# MSXII_SteeringWheelSchematic.net
KiCad netlist of a schematic drawn in Altium Designer
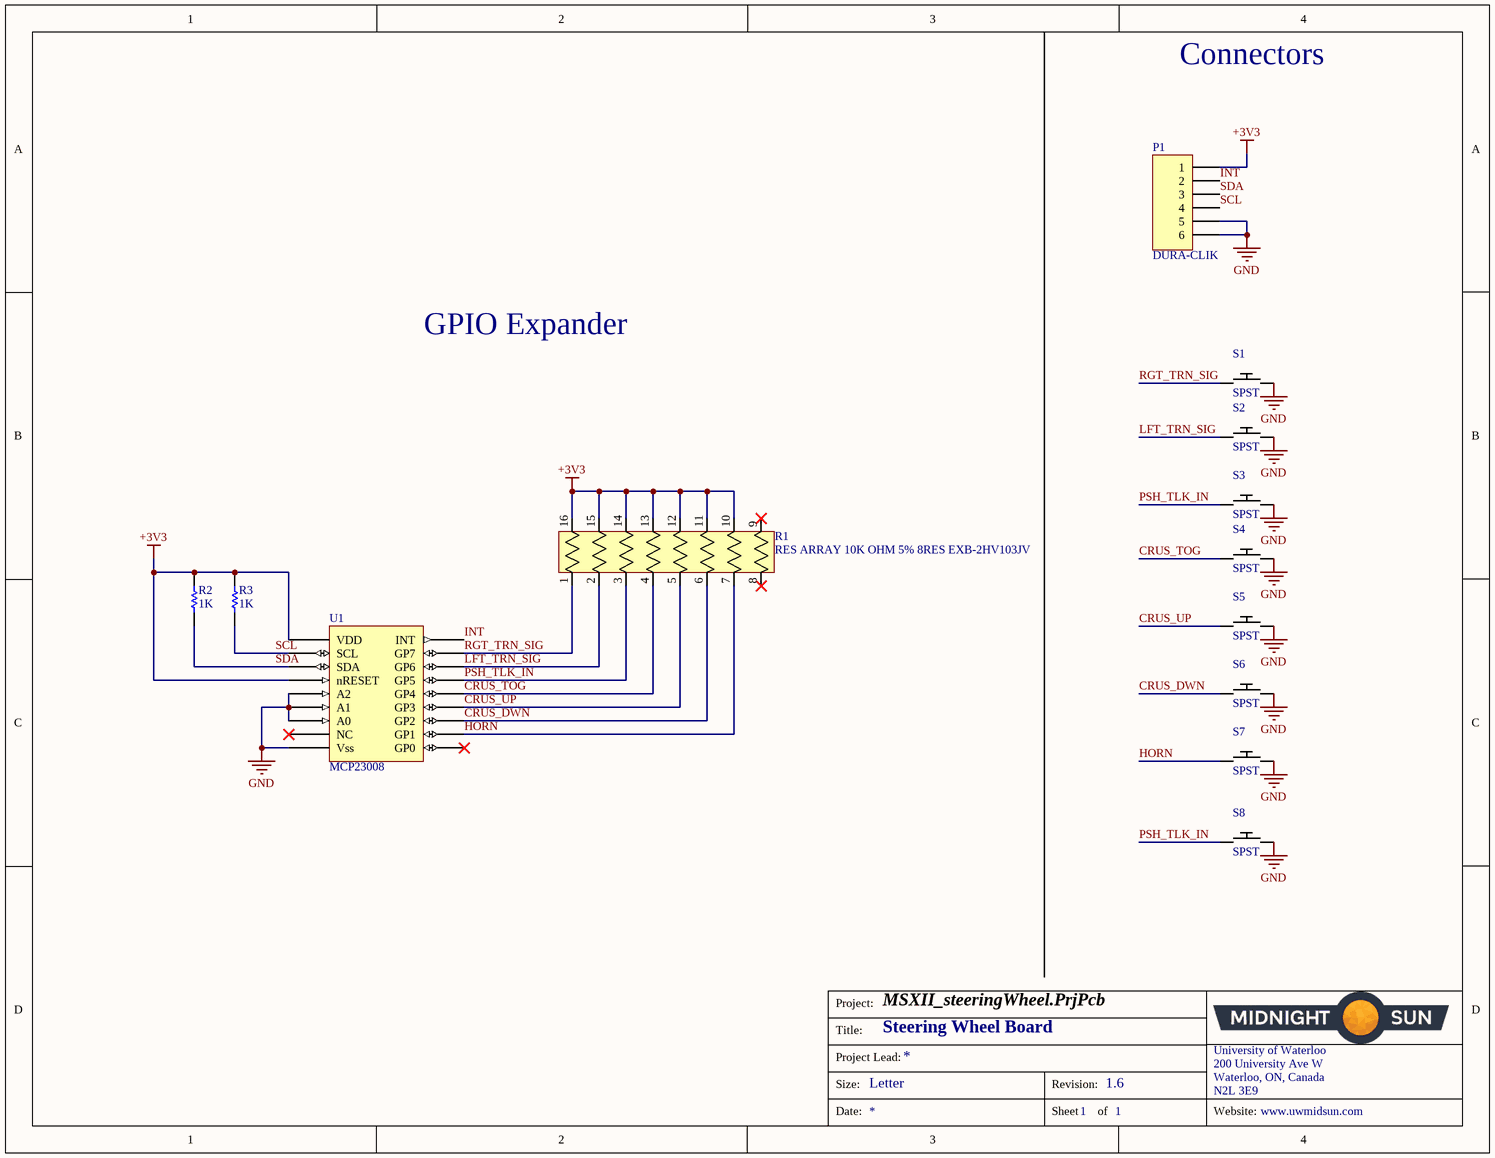
[diagram p0: MSXII_SteeringWheelSchematic.SchDoc]

(export (version "E")
  (design (tool "Eeschema 10.0.6"))
  (components
    (comp (ref "P1")
      (value "DURA-CLIK")
      (footprint "CONN, 6POS DURA-CLIK VERT")
      (description "6 Positions Header, Shrouded Connector 0.079\" (2.00mm) Surface Mount, Vertical Tin")
      (fields (field (name "MANUFACTURER") "Molex") (field (name "MANUFACTURER PART NUMBER") "5600200820"))
      (libsource (lib "Schematic Diagrams") (part "CONN 6POS DURA-CLIK 0.079{dblquote}"))
    )
    (comp (ref "R1")
      (value "RES ARRAY 10K OHM 5% 8RES EXB-2HV103JV")
      (footprint "RES ARRAY, 8 POS 1506")
      (description "RES ARRAY SMD 10K 5% 62.5mW 1506")
      (fields
        (field (name "MANUFACTURER_PART_NUMBER") "EXB-2HV103JV")
        (field (name "COPYRIGHT") "Copyright (C) 2015 Accelerated Designs. All rights reserved")
      )
      (libsource (lib "Schematic Diagrams") (part "RES ARRAY 10K OHM 5% 8RES EXB-2HV103JV"))
    )
    (comp (ref "R2")
      (value "1K")
      (footprint "RES, 0603")
      (description "1k Ohm ±5% 0.1W, 1/10W Chip Resistor 0603 (1608 Metric)")
      (libsource (lib "Schematic Diagrams") (part "RES 1K OHM 5% 1/10W 0603"))
    )
    (comp (ref "R3")
      (value "1K")
      (footprint "RES, 0603")
      (description "1k Ohm ±5% 0.1W, 1/10W Chip Resistor 0603 (1608 Metric)")
      (libsource (lib "Schematic Diagrams") (part "RES 1K OHM 5% 1/10W 0603"))
    )
    (comp (ref "S1")
      (value "SPST")
      (footprint "SW SPST-NO 6x6mm Via Hole")
      (description "Switch Tactile SPST 6x6x9.5mm 15VDC@0.02A Through Hole")
      (libsource (lib "Schematic Diagrams") (part "SW SPST-NO 15VDC@0.02A via hole"))
    )
    (comp (ref "S2")
      (value "SPST")
      (footprint "SW SPST-NO 6x6mm Via Hole")
      (description "Switch Tactile SPST 6x6x9.5mm 15VDC@0.02A Through Hole")
      (libsource (lib "Schematic Diagrams") (part "SW SPST-NO 15VDC@0.02A via hole"))
    )
    (comp (ref "S3")
      (value "SPST")
      (footprint "SW SPST-NO 6x6mm Via Hole")
      (description "Switch Tactile SPST 6x6x9.5mm 15VDC@0.02A Through Hole")
      (libsource (lib "Schematic Diagrams") (part "SW SPST-NO 15VDC@0.02A via hole"))
    )
    (comp (ref "S4")
      (value "SPST")
      (footprint "SW SPST-NO 6x6mm Via Hole")
      (description "Switch Tactile SPST 6x6x9.5mm 15VDC@0.02A Through Hole")
      (libsource (lib "Schematic Diagrams") (part "SW SPST-NO 15VDC@0.02A via hole"))
    )
    (comp (ref "S5")
      (value "SPST")
      (footprint "SW SPST-NO 6x6mm Via Hole")
      (description "Switch Tactile SPST 6x6x9.5mm 15VDC@0.02A Through Hole")
      (libsource (lib "Schematic Diagrams") (part "SW SPST-NO 15VDC@0.02A via hole"))
    )
    (comp (ref "S6")
      (value "SPST")
      (footprint "SW SPST-NO 6x6mm Via Hole")
      (description "Switch Tactile SPST 6x6x9.5mm 15VDC@0.02A Through Hole")
      (libsource (lib "Schematic Diagrams") (part "SW SPST-NO 15VDC@0.02A via hole"))
    )
    (comp (ref "S7")
      (value "SPST")
      (footprint "SW SPST-NO 6x6mm Via Hole")
      (description "Switch Tactile SPST 6x6x9.5mm 15VDC@0.02A Through Hole")
      (libsource (lib "Schematic Diagrams") (part "SW SPST-NO 15VDC@0.02A via hole"))
    )
    (comp (ref "S8")
      (value "SPST")
      (footprint "SW SPST-NO 6x6mm Via Hole")
      (description "Switch Tactile SPST 6x6x9.5mm 15VDC@0.02A Through Hole")
      (libsource (lib "Schematic Diagrams") (part "SW SPST-NO 15VDC@0.02A via hole"))
    )
    (comp (ref "U1")
      (value "MCP23008")
      (footprint "IC 18SOIC")
      (description "MCP23008 I/O Expander 8B+1Int 18P SOIC")
      (libsource (lib "Schematic Diagrams") (part "IC I/O EXPANDER I2C 8B 18SOIC"))
    )
  )
  (nets
    (net (code "1") (name "+3V3") (class "Default")
      (node (ref "P1") (pin "1") (pinfunction "1_1") (pintype "passive"))
      (node (ref "R1") (pin "10") (pinfunction "10_10") (pintype "passive"))
      (node (ref "R1") (pin "11") (pinfunction "11_11") (pintype "passive"))
      (node (ref "R1") (pin "12") (pinfunction "12_12") (pintype "passive"))
      (node (ref "R1") (pin "13") (pinfunction "13_13") (pintype "passive"))
      (node (ref "R1") (pin "14") (pinfunction "14_14") (pintype "passive"))
      (node (ref "R1") (pin "15") (pinfunction "15_15") (pintype "passive"))
      (node (ref "R1") (pin "16") (pinfunction "16_16") (pintype "passive"))
      (node (ref "R2") (pin "1") (pinfunction "1_1") (pintype "passive"))
      (node (ref "R3") (pin "1") (pinfunction "1_1") (pintype "passive"))
      (node (ref "U1") (pin "18") (pinfunction "VDD_18") (pintype "power_in"))
      (node (ref "U1") (pin "6") (pinfunction "nRESET_6") (pintype "input"))
    )
    (net (code "2") (name "/CRUS_DWN") (class "Default")
      (node (ref "R1") (pin "6") (pinfunction "6_6") (pintype "passive"))
      (node (ref "S6") (pin "1") (pinfunction "1_1") (pintype "passive"))
      (node (ref "U1") (pin "12") (pinfunction "GP2_12") (pintype "bidirectional"))
    )
    (net (code "3") (name "/CRUS_TOG") (class "Default")
      (node (ref "R1") (pin "4") (pinfunction "4_4") (pintype "passive"))
      (node (ref "S4") (pin "1") (pinfunction "1_1") (pintype "passive"))
      (node (ref "U1") (pin "14") (pinfunction "GP4_14") (pintype "bidirectional"))
    )
    (net (code "4") (name "/CRUS_UP") (class "Default")
      (node (ref "R1") (pin "5") (pinfunction "5_5") (pintype "passive"))
      (node (ref "S5") (pin "1") (pinfunction "1_1") (pintype "passive"))
      (node (ref "U1") (pin "13") (pinfunction "GP3_13") (pintype "bidirectional"))
    )
    (net (code "5") (name "/HORN") (class "Default")
      (node (ref "R1") (pin "7") (pinfunction "7_7") (pintype "passive"))
      (node (ref "S7") (pin "1") (pinfunction "1_1") (pintype "passive"))
      (node (ref "U1") (pin "11") (pinfunction "GP1_11") (pintype "bidirectional"))
    )
    (net (code "6") (name "/INT") (class "Default")
      (node (ref "P1") (pin "2") (pinfunction "2_2") (pintype "passive"))
      (node (ref "U1") (pin "8") (pinfunction "INT_8") (pintype "output"))
    )
    (net (code "7") (name "/LFT_TRN_SIG") (class "Default")
      (node (ref "R1") (pin "2") (pinfunction "2_2") (pintype "passive"))
      (node (ref "S2") (pin "1") (pinfunction "1_1") (pintype "passive"))
      (node (ref "U1") (pin "16") (pinfunction "GP6_16") (pintype "bidirectional"))
    )
    (net (code "8") (name "/PSH_TLK_IN") (class "Default")
      (node (ref "R1") (pin "3") (pinfunction "3_3") (pintype "passive"))
      (node (ref "S3") (pin "1") (pinfunction "1_1") (pintype "passive"))
      (node (ref "S8") (pin "1") (pinfunction "1_1") (pintype "passive"))
      (node (ref "U1") (pin "15") (pinfunction "GP5_15") (pintype "bidirectional"))
    )
    (net (code "9") (name "/RGT_TRN_SIG") (class "Default")
      (node (ref "R1") (pin "1") (pinfunction "1_1") (pintype "passive"))
      (node (ref "S1") (pin "1") (pinfunction "1_1") (pintype "passive"))
      (node (ref "U1") (pin "17") (pinfunction "GP7_17") (pintype "bidirectional"))
    )
    (net (code "10") (name "/SCL") (class "Default")
      (node (ref "P1") (pin "4") (pinfunction "4_4") (pintype "passive"))
      (node (ref "R3") (pin "2") (pinfunction "2_2") (pintype "passive"))
      (node (ref "U1") (pin "1") (pinfunction "SCL_1") (pintype "bidirectional"))
    )
    (net (code "11") (name "/SDA") (class "Default")
      (node (ref "P1") (pin "3") (pinfunction "3_3") (pintype "passive"))
      (node (ref "R2") (pin "2") (pinfunction "2_2") (pintype "passive"))
      (node (ref "U1") (pin "2") (pinfunction "SDA_2") (pintype "bidirectional"))
    )
    (net (code "12") (name "GND") (class "Default")
      (node (ref "P1") (pin "5") (pinfunction "5_5") (pintype "passive"))
      (node (ref "P1") (pin "6") (pinfunction "6_6") (pintype "passive"))
      (node (ref "S1") (pin "2") (pinfunction "2_2") (pintype "passive"))
      (node (ref "S2") (pin "2") (pinfunction "2_2") (pintype "passive"))
      (node (ref "S3") (pin "2") (pinfunction "2_2") (pintype "passive"))
      (node (ref "S4") (pin "2") (pinfunction "2_2") (pintype "passive"))
      (node (ref "S5") (pin "2") (pinfunction "2_2") (pintype "passive"))
      (node (ref "S6") (pin "2") (pinfunction "2_2") (pintype "passive"))
      (node (ref "S7") (pin "2") (pinfunction "2_2") (pintype "passive"))
      (node (ref "S8") (pin "2") (pinfunction "2_2") (pintype "passive"))
      (node (ref "U1") (pin "3") (pinfunction "A2_3") (pintype "input"))
      (node (ref "U1") (pin "4") (pinfunction "A1_4") (pintype "input"))
      (node (ref "U1") (pin "5") (pinfunction "A0_5") (pintype "input"))
      (node (ref "U1") (pin "9") (pinfunction "Vss_9") (pintype "power_in"))
    )
    (net (code "13") (name "unconnected-(R1-Pad8)") (class "Default")
      (node (ref "R1") (pin "8") (pinfunction "8_8") (pintype "passive+no_connect"))
    )
    (net (code "14") (name "unconnected-(R1-Pad9)") (class "Default")
      (node (ref "R1") (pin "9") (pinfunction "9_9") (pintype "passive+no_connect"))
    )
    (net (code "15") (name "unconnected-(U1-GP0-Pad10)") (class "Default")
      (node (ref "U1") (pin "10") (pinfunction "GP0_10") (pintype "bidirectional+no_connect"))
    )
    (net (code "16") (name "unconnected-(U1-NC-Pad7)") (class "Default")
      (node (ref "U1") (pin "7") (pinfunction "NC_7") (pintype "passive+no_connect"))
    )
  )
)
